# PicoKey.net
KiCad netlist of a schematic drawn in EasyEDA Pro
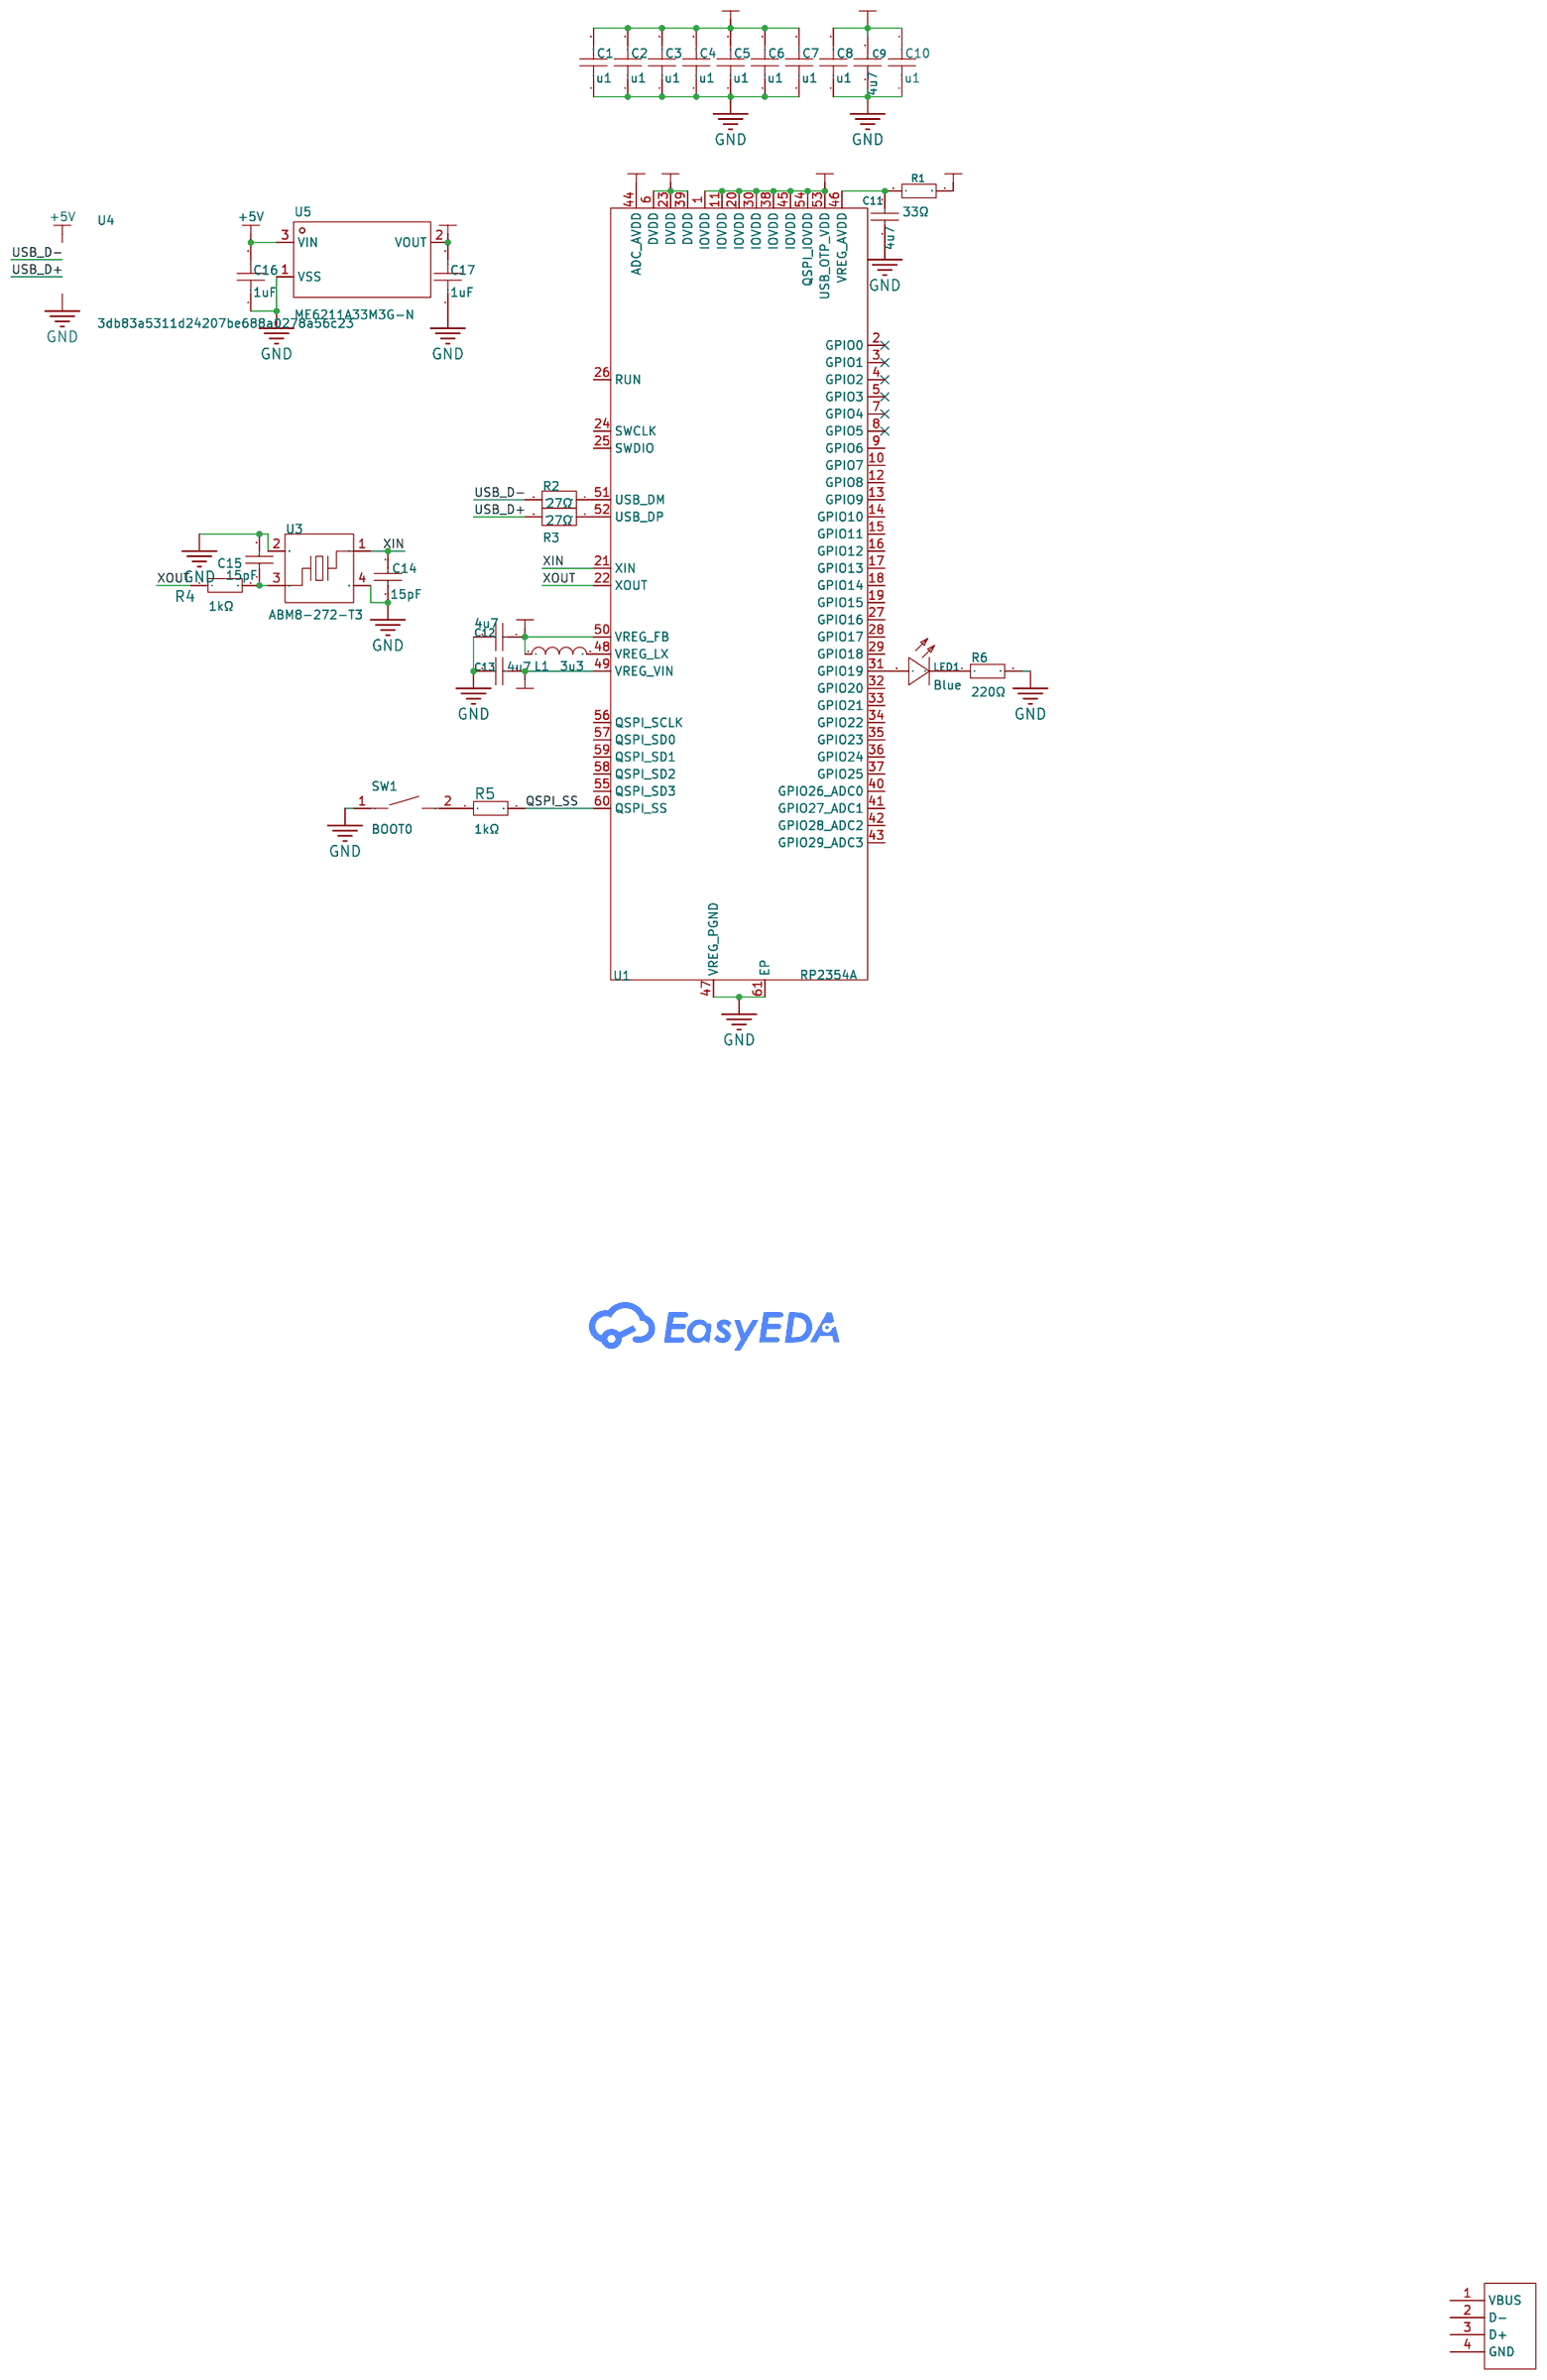
[diagram p0: schematic sheet]

(export (version "E")
  (design (tool "Eeschema 10.0.6"))
  (components
    (comp (ref "C1")
      (value "u1")
      (footprint "easyedapro:C0402")
      (description "Capacitance:100nF Tolerance:±10% Tolerance:±10% Voltage Rating:16V Temperature Coefficient:X7R")
      (fields
        (field (name "Manufacturer Part") "CL05B104KO5NNNC")
        (field (name "Manufacturer") "SAMSUNG(三星)")
      )
      (libsource (lib "easyedapro") (part "CL05B104KO5NNNC"))
    )
    (comp (ref "C2")
      (value "u1")
      (footprint "easyedapro:C0402")
      (description "Capacitance:100nF Tolerance:±10% Tolerance:±10% Voltage Rating:16V Temperature Coefficient:X7R")
      (fields
        (field (name "Manufacturer Part") "CL05B104KO5NNNC")
        (field (name "Manufacturer") "SAMSUNG(三星)")
      )
      (libsource (lib "easyedapro") (part "CL05B104KO5NNNC"))
    )
    (comp (ref "C3")
      (value "u1")
      (footprint "easyedapro:C0402")
      (description "Capacitance:100nF Tolerance:±10% Tolerance:±10% Voltage Rating:16V Temperature Coefficient:X7R")
      (fields
        (field (name "Manufacturer Part") "CL05B104KO5NNNC")
        (field (name "Manufacturer") "SAMSUNG(三星)")
      )
      (libsource (lib "easyedapro") (part "CL05B104KO5NNNC"))
    )
    (comp (ref "C4")
      (value "u1")
      (footprint "easyedapro:C0402")
      (description "Capacitance:100nF Tolerance:±10% Tolerance:±10% Voltage Rating:16V Temperature Coefficient:X7R")
      (fields
        (field (name "Manufacturer Part") "CL05B104KO5NNNC")
        (field (name "Manufacturer") "SAMSUNG(三星)")
      )
      (libsource (lib "easyedapro") (part "CL05B104KO5NNNC"))
    )
    (comp (ref "C5")
      (value "u1")
      (footprint "easyedapro:C0402")
      (description "Capacitance:100nF Tolerance:±10% Tolerance:±10% Voltage Rating:16V Temperature Coefficient:X7R")
      (fields
        (field (name "Manufacturer Part") "CL05B104KO5NNNC")
        (field (name "Manufacturer") "SAMSUNG(三星)")
      )
      (libsource (lib "easyedapro") (part "CL05B104KO5NNNC"))
    )
    (comp (ref "C6")
      (value "u1")
      (footprint "easyedapro:C0402")
      (description "Capacitance:100nF Tolerance:±10% Tolerance:±10% Voltage Rating:16V Temperature Coefficient:X7R")
      (fields
        (field (name "Manufacturer Part") "CL05B104KO5NNNC")
        (field (name "Manufacturer") "SAMSUNG(三星)")
      )
      (libsource (lib "easyedapro") (part "CL05B104KO5NNNC"))
    )
    (comp (ref "C7")
      (value "u1")
      (footprint "easyedapro:C0402")
      (description "Capacitance:100nF Tolerance:±10% Tolerance:±10% Voltage Rating:16V Temperature Coefficient:X7R")
      (fields
        (field (name "Manufacturer Part") "CL05B104KO5NNNC")
        (field (name "Manufacturer") "SAMSUNG(三星)")
      )
      (libsource (lib "easyedapro") (part "CL05B104KO5NNNC"))
    )
    (comp (ref "C8")
      (value "u1")
      (footprint "easyedapro:C0402")
      (description "Capacitance:100nF Tolerance:±10% Tolerance:±10% Voltage Rating:16V Temperature Coefficient:X7R")
      (fields
        (field (name "Manufacturer Part") "CL05B104KO5NNNC")
        (field (name "Manufacturer") "SAMSUNG(三星)")
      )
      (libsource (lib "easyedapro") (part "CL05B104KO5NNNC"))
    )
    (comp (ref "C9")
      (value "4u7")
      (footprint "easyedapro:C0402")
      (description "Capacitance:4.7uF Tolerance:±20% Tolerance:±20% Voltage Rating:10V Temperature Coefficient:X5R")
      (fields
        (field (name "Manufacturer Part") "CL05A475MP5NRNC")
        (field (name "Manufacturer") "SAMSUNG(三星)")
      )
      (libsource (lib "easyedapro") (part "CL05A475MP5NRNC"))
    )
    (comp (ref "C10")
      (value "u1")
      (footprint "easyedapro:C0402")
      (description "Capacitance:100nF Tolerance:±10% Tolerance:±10% Voltage Rating:16V Temperature Coefficient:X7R")
      (fields
        (field (name "Manufacturer Part") "CL05B104KO5NNNC")
        (field (name "Manufacturer") "SAMSUNG(三星)")
      )
      (libsource (lib "easyedapro") (part "CL05B104KO5NNNC"))
    )
    (comp (ref "C11")
      (value "4u7")
      (footprint "easyedapro:C0402")
      (description "Capacitance:4.7uF Tolerance:±20% Tolerance:±20% Voltage Rating:10V Temperature Coefficient:X5R")
      (fields
        (field (name "Manufacturer Part") "CL05A475MP5NRNC")
        (field (name "Manufacturer") "SAMSUNG(三星)")
      )
      (libsource (lib "easyedapro") (part "CL05A475MP5NRNC"))
    )
    (comp (ref "C12")
      (value "4u7")
      (footprint "easyedapro:C0402")
      (description "Capacitance:4.7uF Tolerance:±20% Tolerance:±20% Voltage Rating:10V Temperature Coefficient:X5R")
      (fields
        (field (name "Manufacturer Part") "CL05A475MP5NRNC")
        (field (name "Manufacturer") "SAMSUNG(三星)")
      )
      (libsource (lib "easyedapro") (part "CL05A475MP5NRNC"))
    )
    (comp (ref "C13")
      (value "4u7")
      (footprint "easyedapro:C0402")
      (description "Capacitance:4.7uF Tolerance:±20% Tolerance:±20% Voltage Rating:10V Temperature Coefficient:X5R")
      (fields
        (field (name "Manufacturer Part") "CL05A475MP5NRNC")
        (field (name "Manufacturer") "SAMSUNG(三星)")
      )
      (libsource (lib "easyedapro") (part "CL05A475MP5NRNC"))
    )
    (comp (ref "C14")
      (value "15pF")
      (footprint "easyedapro:C0402")
      (fields (field (name "Manufacturer Part") "0402CG150J500NT") (field (name "Manufacturer") "FH(风华)"))
      (libsource (lib "easyedapro") (part "0402CG150J500NT"))
    )
    (comp (ref "C15")
      (value "15pF")
      (footprint "easyedapro:C0402")
      (fields (field (name "Manufacturer Part") "0402CG150J500NT") (field (name "Manufacturer") "FH(风华)"))
      (libsource (lib "easyedapro") (part "0402CG150J500NT"))
    )
    (comp (ref "C16")
      (value "1uF")
      (footprint "easyedapro:C0402")
      (description "Capacitance:1uF Tolerance:±10% Tolerance:±10% Voltage Rating:25V Temperature Coefficient:X5R")
      (fields
        (field (name "Manufacturer Part") "CL05A105KA5NQNC")
        (field (name "Manufacturer") "SAMSUNG(三星)")
      )
      (libsource (lib "easyedapro") (part "CL05A105KA5NQNC"))
    )
    (comp (ref "C17")
      (value "1uF")
      (footprint "easyedapro:C0402")
      (description "Capacitance:1uF Tolerance:±10% Tolerance:±10% Voltage Rating:25V Temperature Coefficient:X5R")
      (fields
        (field (name "Manufacturer Part") "CL05A105KA5NQNC")
        (field (name "Manufacturer") "SAMSUNG(三星)")
      )
      (libsource (lib "easyedapro") (part "CL05A105KA5NQNC"))
    )
    (comp (ref "L1")
      (value "3u3")
      (footprint "easyedapro:IND-SMD_L2.0-W1.6_AOTA-B201610S3R3-101-T")
      (fields (field (name "Manufacturer") "ABRACON"))
      (libsource (lib "easyedapro") (part "AOTA-B201610S3R3-101-T"))
    )
    (comp (ref "LED1")
      (value "Blue")
      (footprint "easyedapro:LED0402-RD_BLUE")
      (fields (field (name "Manufacturer") "MEIHUA(美华)"))
      (libsource (lib "easyedapro") (part "MHT136UBCT"))
    )
    (comp (ref "R1")
      (value "33Ω")
      (footprint "easyedapro:R0402")
      (fields
        (field (name "Manufacturer Part") "0402WGF330JTCE")
        (field (name "Manufacturer") "UNI-ROYAL(厚声)")
      )
      (libsource (lib "easyedapro") (part "0402WGF330JTCE"))
    )
    (comp (ref "R2")
      (value "27Ω")
      (footprint "easyedapro:R0402")
      (fields (field (name "Manufacturer Part") "WR04X270JTL") (field (name "Manufacturer") "Walsin(华新科)"))
      (libsource (lib "easyedapro") (part "WR04X270 JTL"))
    )
    (comp (ref "R3")
      (value "27Ω")
      (footprint "easyedapro:R0402")
      (fields (field (name "Manufacturer Part") "WR04X270JTL") (field (name "Manufacturer") "Walsin(华新科)"))
      (libsource (lib "easyedapro") (part "WR04X270 JTL"))
    )
    (comp (ref "R4")
      (value "1kΩ")
      (footprint "easyedapro:R0402")
      (fields
        (field (name "Manufacturer Part") "0402WGF1001TCE")
        (field (name "Manufacturer") "UNI-ROYAL(厚声)")
      )
      (libsource (lib "easyedapro") (part "0402WGF1001TCE"))
    )
    (comp (ref "R5")
      (value "1kΩ")
      (footprint "easyedapro:R0402")
      (fields
        (field (name "Manufacturer Part") "0402WGF1001TCE")
        (field (name "Manufacturer") "UNI-ROYAL(厚声)")
      )
      (libsource (lib "easyedapro") (part "0402WGF1001TCE"))
    )
    (comp (ref "R6")
      (value "220Ω")
      (footprint "easyedapro:R0402")
      (fields (field (name "Manufacturer Part") "RC0402FR-07220RL") (field (name "Manufacturer") "YAGEO(国巨)"))
      (libsource (lib "easyedapro") (part "RC0402FR-07220RL"))
    )
    (comp (ref "SW1")
      (value "BOOT0")
      (footprint "easyedapro:SW-SMD_L3.9-W3.0-P4.45")
      (fields (field (name "Manufacturer") "XUNPU(讯普)"))
      (libsource (lib "easyedapro") (part "TS-1088-AR02016"))
    )
    (comp (ref "U1")
      (value "RP2354A")
      (footprint "easyedapro:QFN-60_L7.0-W7.0-P0.40-TL-EP3.4")
      (fields (field (name "Manufacturer") "Raspberry Pi(树莓派)"))
      (libsource (lib "easyedapro") (part "RP2354A"))
    )
    (comp (ref "U3")
      (value "ABM8-272-T3")
      (footprint "easyedapro:CRYSTAL-SMD_4P-L3.2-W2.5-BL")
      (fields (field (name "Manufacturer") "ABRACON"))
      (libsource (lib "easyedapro") (part "ABM8-272-T3_C20625731"))
    )
    (comp (ref "U4")
      (value "3db83a5311d24207be688a0278a56c23")
      (footprint "easyedapro:USB-A_PCB")
      (libsource (lib "easyedapro") (part "USB-A_PCB"))
    )
    (comp (ref "U5")
      (value "ME6211A33M3G-N")
      (footprint "easyedapro:SOT-23-3_L2.9-W1.6-P1.90-LS2.8-BR")
      (fields (field (name "Manufacturer") "MICRONE(南京微盟)"))
      (libsource (lib "easyedapro") (part "ME6211A33M3G-N"))
    )
  )
  (nets
    (net (code "1") (name "+1V1") (class "Default")
      (node (ref "C10") (pin "2") (pinfunction "2_2") (pintype "unspecified"))
      (node (ref "C12") (pin "1") (pinfunction "1_1") (pintype "input"))
      (node (ref "C8") (pin "2") (pinfunction "2_2") (pintype "unspecified"))
      (node (ref "C9") (pin "2") (pinfunction "2_2") (pintype "input"))
      (node (ref "L1") (pin "1") (pinfunction "1_1") (pintype "unspecified"))
      (node (ref "U1") (pin "23") (pinfunction "DVDD_23") (pintype "unspecified"))
      (node (ref "U1") (pin "39") (pinfunction "DVDD_39") (pintype "unspecified"))
      (node (ref "U1") (pin "50") (pinfunction "VREG_FB_50") (pintype "unspecified"))
      (node (ref "U1") (pin "6") (pinfunction "DVDD_6") (pintype "unspecified"))
    )
    (net (code "2") (name "+3V3") (class "Default")
      (node (ref "C1") (pin "2") (pinfunction "2_2") (pintype "unspecified"))
      (node (ref "C13") (pin "1") (pinfunction "1_1") (pintype "input"))
      (node (ref "C17") (pin "2") (pinfunction "2_2") (pintype "unspecified"))
      (node (ref "C2") (pin "2") (pinfunction "2_2") (pintype "unspecified"))
      (node (ref "C3") (pin "2") (pinfunction "2_2") (pintype "unspecified"))
      (node (ref "C4") (pin "2") (pinfunction "2_2") (pintype "unspecified"))
      (node (ref "C5") (pin "2") (pinfunction "2_2") (pintype "unspecified"))
      (node (ref "C6") (pin "2") (pinfunction "2_2") (pintype "unspecified"))
      (node (ref "C7") (pin "2") (pinfunction "2_2") (pintype "unspecified"))
      (node (ref "R1") (pin "2") (pinfunction "2_2") (pintype "input"))
      (node (ref "U1") (pin "1") (pinfunction "IOVDD_1") (pintype "unspecified"))
      (node (ref "U1") (pin "11") (pinfunction "IOVDD_11") (pintype "unspecified"))
      (node (ref "U1") (pin "20") (pinfunction "IOVDD_20") (pintype "unspecified"))
      (node (ref "U1") (pin "30") (pinfunction "IOVDD_30") (pintype "unspecified"))
      (node (ref "U1") (pin "38") (pinfunction "IOVDD_38") (pintype "unspecified"))
      (node (ref "U1") (pin "44") (pinfunction "ADC_AVDD_44") (pintype "unspecified"))
      (node (ref "U1") (pin "45") (pinfunction "IOVDD_45") (pintype "unspecified"))
      (node (ref "U1") (pin "49") (pinfunction "VREG_VIN_49") (pintype "unspecified"))
      (node (ref "U1") (pin "53") (pinfunction "USB_OTP_VDD_53") (pintype "unspecified"))
      (node (ref "U1") (pin "54") (pinfunction "QSPI_IOVDD_54") (pintype "unspecified"))
      (node (ref "U5") (pin "2") (pinfunction "VOUT_2") (pintype "input"))
    )
    (net (code "3") (name "+5V") (class "Default")
      (node (ref "C16") (pin "2") (pinfunction "2_2") (pintype "unspecified"))
      (node (ref "U5") (pin "3") (pinfunction "VIN_3") (pintype "input"))
    )
    (net (code "4") (name "/QSPI_SS") (class "Default")
      (node (ref "R5") (pin "2") (pinfunction "2_2") (pintype "input"))
      (node (ref "U1") (pin "60") (pinfunction "QSPI_SS_60") (pintype "unspecified"))
    )
    (net (code "5") (name "/USB_D+") (class "Default")
      (node (ref "R3") (pin "2") (pinfunction "2_2") (pintype "unspecified"))
    )
    (net (code "6") (name "/USB_D-") (class "Default")
      (node (ref "R2") (pin "2") (pinfunction "2_2") (pintype "unspecified"))
    )
    (net (code "7") (name "/XIN") (class "Default")
      (node (ref "C14") (pin "2") (pinfunction "2_2") (pintype "input"))
      (node (ref "U1") (pin "21") (pinfunction "XIN_21") (pintype "unspecified"))
      (node (ref "U3") (pin "1") (pinfunction "1_1") (pintype "input"))
    )
    (net (code "8") (name "/XOUT") (class "Default")
      (node (ref "R4") (pin "1") (pinfunction "1_1") (pintype "input"))
      (node (ref "U1") (pin "22") (pinfunction "XOUT_22") (pintype "unspecified"))
    )
    (net (code "9") (name "GND") (class "Default")
      (node (ref "C1") (pin "1") (pinfunction "1_1") (pintype "unspecified"))
      (node (ref "C10") (pin "1") (pinfunction "1_1") (pintype "unspecified"))
      (node (ref "C11") (pin "1") (pinfunction "1_1") (pintype "input"))
      (node (ref "C12") (pin "2") (pinfunction "2_2") (pintype "input"))
      (node (ref "C13") (pin "2") (pinfunction "2_2") (pintype "input"))
      (node (ref "C14") (pin "1") (pinfunction "1_1") (pintype "input"))
      (node (ref "C15") (pin "2") (pinfunction "2_2") (pintype "input"))
      (node (ref "C16") (pin "1") (pinfunction "1_1") (pintype "unspecified"))
      (node (ref "C17") (pin "1") (pinfunction "1_1") (pintype "unspecified"))
      (node (ref "C2") (pin "1") (pinfunction "1_1") (pintype "unspecified"))
      (node (ref "C3") (pin "1") (pinfunction "1_1") (pintype "unspecified"))
      (node (ref "C4") (pin "1") (pinfunction "1_1") (pintype "unspecified"))
      (node (ref "C5") (pin "1") (pinfunction "1_1") (pintype "unspecified"))
      (node (ref "C6") (pin "1") (pinfunction "1_1") (pintype "unspecified"))
      (node (ref "C7") (pin "1") (pinfunction "1_1") (pintype "unspecified"))
      (node (ref "C8") (pin "1") (pinfunction "1_1") (pintype "unspecified"))
      (node (ref "C9") (pin "1") (pinfunction "1_1") (pintype "input"))
      (node (ref "R6") (pin "2") (pinfunction "2_2") (pintype "input"))
      (node (ref "SW1") (pin "1") (pinfunction "1_1") (pintype "unspecified"))
      (node (ref "U1") (pin "47") (pinfunction "VREG_PGND_47") (pintype "unspecified"))
      (node (ref "U1") (pin "61") (pinfunction "EP_61") (pintype "unspecified"))
      (node (ref "U3") (pin "2") (pinfunction "GND_2") (pintype "input"))
      (node (ref "U3") (pin "4") (pinfunction "GND_4") (pintype "input"))
      (node (ref "U5") (pin "1") (pinfunction "VSS_1") (pintype "input"))
    )
    (net (code "10") (name "Net-(C15-Pad1)") (class "Default")
      (node (ref "C15") (pin "1") (pinfunction "1_1") (pintype "input"))
      (node (ref "R4") (pin "2") (pinfunction "2_2") (pintype "input"))
      (node (ref "U3") (pin "3") (pinfunction "3_3") (pintype "input"))
    )
    (net (code "11") (name "Net-(LED1-A)") (class "Default")
      (node (ref "LED1") (pin "2") (pinfunction "A_2") (pintype "input"))
      (node (ref "U1") (pin "31") (pinfunction "GPIO19_31") (pintype "unspecified"))
    )
    (net (code "12") (name "Net-(LED1-K)") (class "Default")
      (node (ref "LED1") (pin "1") (pinfunction "K_1") (pintype "input"))
      (node (ref "R6") (pin "1") (pinfunction "1_1") (pintype "input"))
    )
    (net (code "13") (name "Net-(R5-Pad1)") (class "Default")
      (node (ref "R5") (pin "1") (pinfunction "1_1") (pintype "input"))
      (node (ref "SW1") (pin "2") (pinfunction "2_2") (pintype "unspecified"))
    )
    (net (code "14") (name "Net-(U1-USB_DM)") (class "Default")
      (node (ref "R2") (pin "1") (pinfunction "1_1") (pintype "unspecified"))
      (node (ref "U1") (pin "51") (pinfunction "USB_DM_51") (pintype "unspecified"))
    )
    (net (code "15") (name "Net-(U1-USB_DP)") (class "Default")
      (node (ref "R3") (pin "1") (pinfunction "1_1") (pintype "unspecified"))
      (node (ref "U1") (pin "52") (pinfunction "USB_DP_52") (pintype "unspecified"))
    )
    (net (code "16") (name "Net-(U1-VREG_AVDD)") (class "Default")
      (node (ref "C11") (pin "2") (pinfunction "2_2") (pintype "input"))
      (node (ref "R1") (pin "1") (pinfunction "1_1") (pintype "input"))
      (node (ref "U1") (pin "46") (pinfunction "VREG_AVDD_46") (pintype "unspecified"))
    )
    (net (code "17") (name "Net-(U1-VREG_LX)") (class "Default")
      (node (ref "L1") (pin "2") (pinfunction "2_2") (pintype "unspecified"))
      (node (ref "U1") (pin "48") (pinfunction "VREG_LX_48") (pintype "unspecified"))
    )
    (net (code "18") (name "unconnected-(U1-GPIO0-Pad2)") (class "Default")
      (node (ref "U1") (pin "2") (pinfunction "GPIO0_2") (pintype "unspecified+no_connect"))
    )
    (net (code "19") (name "unconnected-(U1-GPIO1-Pad3)") (class "Default")
      (node (ref "U1") (pin "3") (pinfunction "GPIO1_3") (pintype "unspecified+no_connect"))
    )
    (net (code "20") (name "unconnected-(U1-GPIO2-Pad4)") (class "Default")
      (node (ref "U1") (pin "4") (pinfunction "GPIO2_4") (pintype "unspecified+no_connect"))
    )
    (net (code "21") (name "unconnected-(U1-GPIO3-Pad5)") (class "Default")
      (node (ref "U1") (pin "5") (pinfunction "GPIO3_5") (pintype "unspecified+no_connect"))
    )
    (net (code "22") (name "unconnected-(U1-GPIO4-Pad7)") (class "Default")
      (node (ref "U1") (pin "7") (pinfunction "GPIO4_7") (pintype "unspecified+no_connect"))
    )
    (net (code "23") (name "unconnected-(U1-GPIO5-Pad8)") (class "Default")
      (node (ref "U1") (pin "8") (pinfunction "GPIO5_8") (pintype "unspecified+no_connect"))
    )
    (net (code "24") (name "unconnected-(U1-GPIO6-Pad9)") (class "Default")
      (node (ref "U1") (pin "9") (pinfunction "GPIO6_9") (pintype "unspecified"))
    )
    (net (code "25") (name "unconnected-(U1-GPIO7-Pad10)") (class "Default")
      (node (ref "U1") (pin "10") (pinfunction "GPIO7_10") (pintype "unspecified"))
    )
    (net (code "26") (name "unconnected-(U1-GPIO8-Pad12)") (class "Default")
      (node (ref "U1") (pin "12") (pinfunction "GPIO8_12") (pintype "unspecified"))
    )
    (net (code "27") (name "unconnected-(U1-GPIO9-Pad13)") (class "Default")
      (node (ref "U1") (pin "13") (pinfunction "GPIO9_13") (pintype "unspecified"))
    )
    (net (code "28") (name "unconnected-(U1-GPIO10-Pad14)") (class "Default")
      (node (ref "U1") (pin "14") (pinfunction "GPIO10_14") (pintype "unspecified"))
    )
    (net (code "29") (name "unconnected-(U1-GPIO11-Pad15)") (class "Default")
      (node (ref "U1") (pin "15") (pinfunction "GPIO11_15") (pintype "unspecified"))
    )
    (net (code "30") (name "unconnected-(U1-GPIO12-Pad16)") (class "Default")
      (node (ref "U1") (pin "16") (pinfunction "GPIO12_16") (pintype "unspecified"))
    )
    (net (code "31") (name "unconnected-(U1-GPIO13-Pad17)") (class "Default")
      (node (ref "U1") (pin "17") (pinfunction "GPIO13_17") (pintype "unspecified"))
    )
    (net (code "32") (name "unconnected-(U1-GPIO14-Pad18)") (class "Default")
      (node (ref "U1") (pin "18") (pinfunction "GPIO14_18") (pintype "unspecified"))
    )
    (net (code "33") (name "unconnected-(U1-GPIO15-Pad19)") (class "Default")
      (node (ref "U1") (pin "19") (pinfunction "GPIO15_19") (pintype "unspecified"))
    )
    (net (code "34") (name "unconnected-(U1-GPIO16-Pad27)") (class "Default")
      (node (ref "U1") (pin "27") (pinfunction "GPIO16_27") (pintype "unspecified"))
    )
    (net (code "35") (name "unconnected-(U1-GPIO17-Pad28)") (class "Default")
      (node (ref "U1") (pin "28") (pinfunction "GPIO17_28") (pintype "unspecified"))
    )
    (net (code "36") (name "unconnected-(U1-GPIO18-Pad29)") (class "Default")
      (node (ref "U1") (pin "29") (pinfunction "GPIO18_29") (pintype "unspecified"))
    )
    (net (code "37") (name "unconnected-(U1-GPIO20-Pad32)") (class "Default")
      (node (ref "U1") (pin "32") (pinfunction "GPIO20_32") (pintype "unspecified"))
    )
    (net (code "38") (name "unconnected-(U1-GPIO21-Pad33)") (class "Default")
      (node (ref "U1") (pin "33") (pinfunction "GPIO21_33") (pintype "unspecified"))
    )
    (net (code "39") (name "unconnected-(U1-GPIO22-Pad34)") (class "Default")
      (node (ref "U1") (pin "34") (pinfunction "GPIO22_34") (pintype "unspecified"))
    )
    (net (code "40") (name "unconnected-(U1-GPIO23-Pad35)") (class "Default")
      (node (ref "U1") (pin "35") (pinfunction "GPIO23_35") (pintype "unspecified"))
    )
    (net (code "41") (name "unconnected-(U1-GPIO24-Pad36)") (class "Default")
      (node (ref "U1") (pin "36") (pinfunction "GPIO24_36") (pintype "unspecified"))
    )
    (net (code "42") (name "unconnected-(U1-GPIO25-Pad37)") (class "Default")
      (node (ref "U1") (pin "37") (pinfunction "GPIO25_37") (pintype "unspecified"))
    )
    (net (code "43") (name "unconnected-(U1-GPIO26_ADC0-Pad40)") (class "Default")
      (node (ref "U1") (pin "40") (pinfunction "GPIO26_ADC0_40") (pintype "unspecified"))
    )
    (net (code "44") (name "unconnected-(U1-GPIO27_ADC1-Pad41)") (class "Default")
      (node (ref "U1") (pin "41") (pinfunction "GPIO27_ADC1_41") (pintype "unspecified"))
    )
    (net (code "45") (name "unconnected-(U1-GPIO28_ADC2-Pad42)") (class "Default")
      (node (ref "U1") (pin "42") (pinfunction "GPIO28_ADC2_42") (pintype "unspecified"))
    )
    (net (code "46") (name "unconnected-(U1-GPIO29_ADC3-Pad43)") (class "Default")
      (node (ref "U1") (pin "43") (pinfunction "GPIO29_ADC3_43") (pintype "unspecified"))
    )
    (net (code "47") (name "unconnected-(U1-QSPI_SCLK-Pad56)") (class "Default")
      (node (ref "U1") (pin "56") (pinfunction "QSPI_SCLK_56") (pintype "unspecified"))
    )
    (net (code "48") (name "unconnected-(U1-QSPI_SD0-Pad57)") (class "Default")
      (node (ref "U1") (pin "57") (pinfunction "QSPI_SD0_57") (pintype "unspecified"))
    )
    (net (code "49") (name "unconnected-(U1-QSPI_SD1-Pad59)") (class "Default")
      (node (ref "U1") (pin "59") (pinfunction "QSPI_SD1_59") (pintype "unspecified"))
    )
    (net (code "50") (name "unconnected-(U1-QSPI_SD2-Pad58)") (class "Default")
      (node (ref "U1") (pin "58") (pinfunction "QSPI_SD2_58") (pintype "unspecified"))
    )
    (net (code "51") (name "unconnected-(U1-QSPI_SD3-Pad55)") (class "Default")
      (node (ref "U1") (pin "55") (pinfunction "QSPI_SD3_55") (pintype "unspecified"))
    )
    (net (code "52") (name "unconnected-(U1-RUN-Pad26)") (class "Default")
      (node (ref "U1") (pin "26") (pinfunction "RUN_26") (pintype "unspecified"))
    )
    (net (code "53") (name "unconnected-(U1-SWCLK-Pad24)") (class "Default")
      (node (ref "U1") (pin "24") (pinfunction "SWCLK_24") (pintype "unspecified"))
    )
    (net (code "54") (name "unconnected-(U1-SWDIO-Pad25)") (class "Default")
      (node (ref "U1") (pin "25") (pinfunction "SWDIO_25") (pintype "unspecified"))
    )
    (net (code "55") (name "unconnected-(U4-D+-Pad3)") (class "Default")
      (node (ref "U4") (pin "3") (pinfunction "D+_3") (pintype "input"))
    )
    (net (code "56") (name "unconnected-(U4-D--Pad2)") (class "Default")
      (node (ref "U4") (pin "2") (pinfunction "D-_2") (pintype "input"))
    )
    (net (code "57") (name "unconnected-(U4-GND-Pad4)") (class "Default")
      (node (ref "U4") (pin "4") (pinfunction "GND_4") (pintype "input"))
    )
    (net (code "58") (name "unconnected-(U4-VBUS-Pad1)") (class "Default")
      (node (ref "U4") (pin "1") (pinfunction "VBUS_1") (pintype "input"))
    )
  )
)
